# ESP32_Bedsensor_Dual_with_BME_30pin.net
KiCad netlist of a schematic drawn in EasyEDA
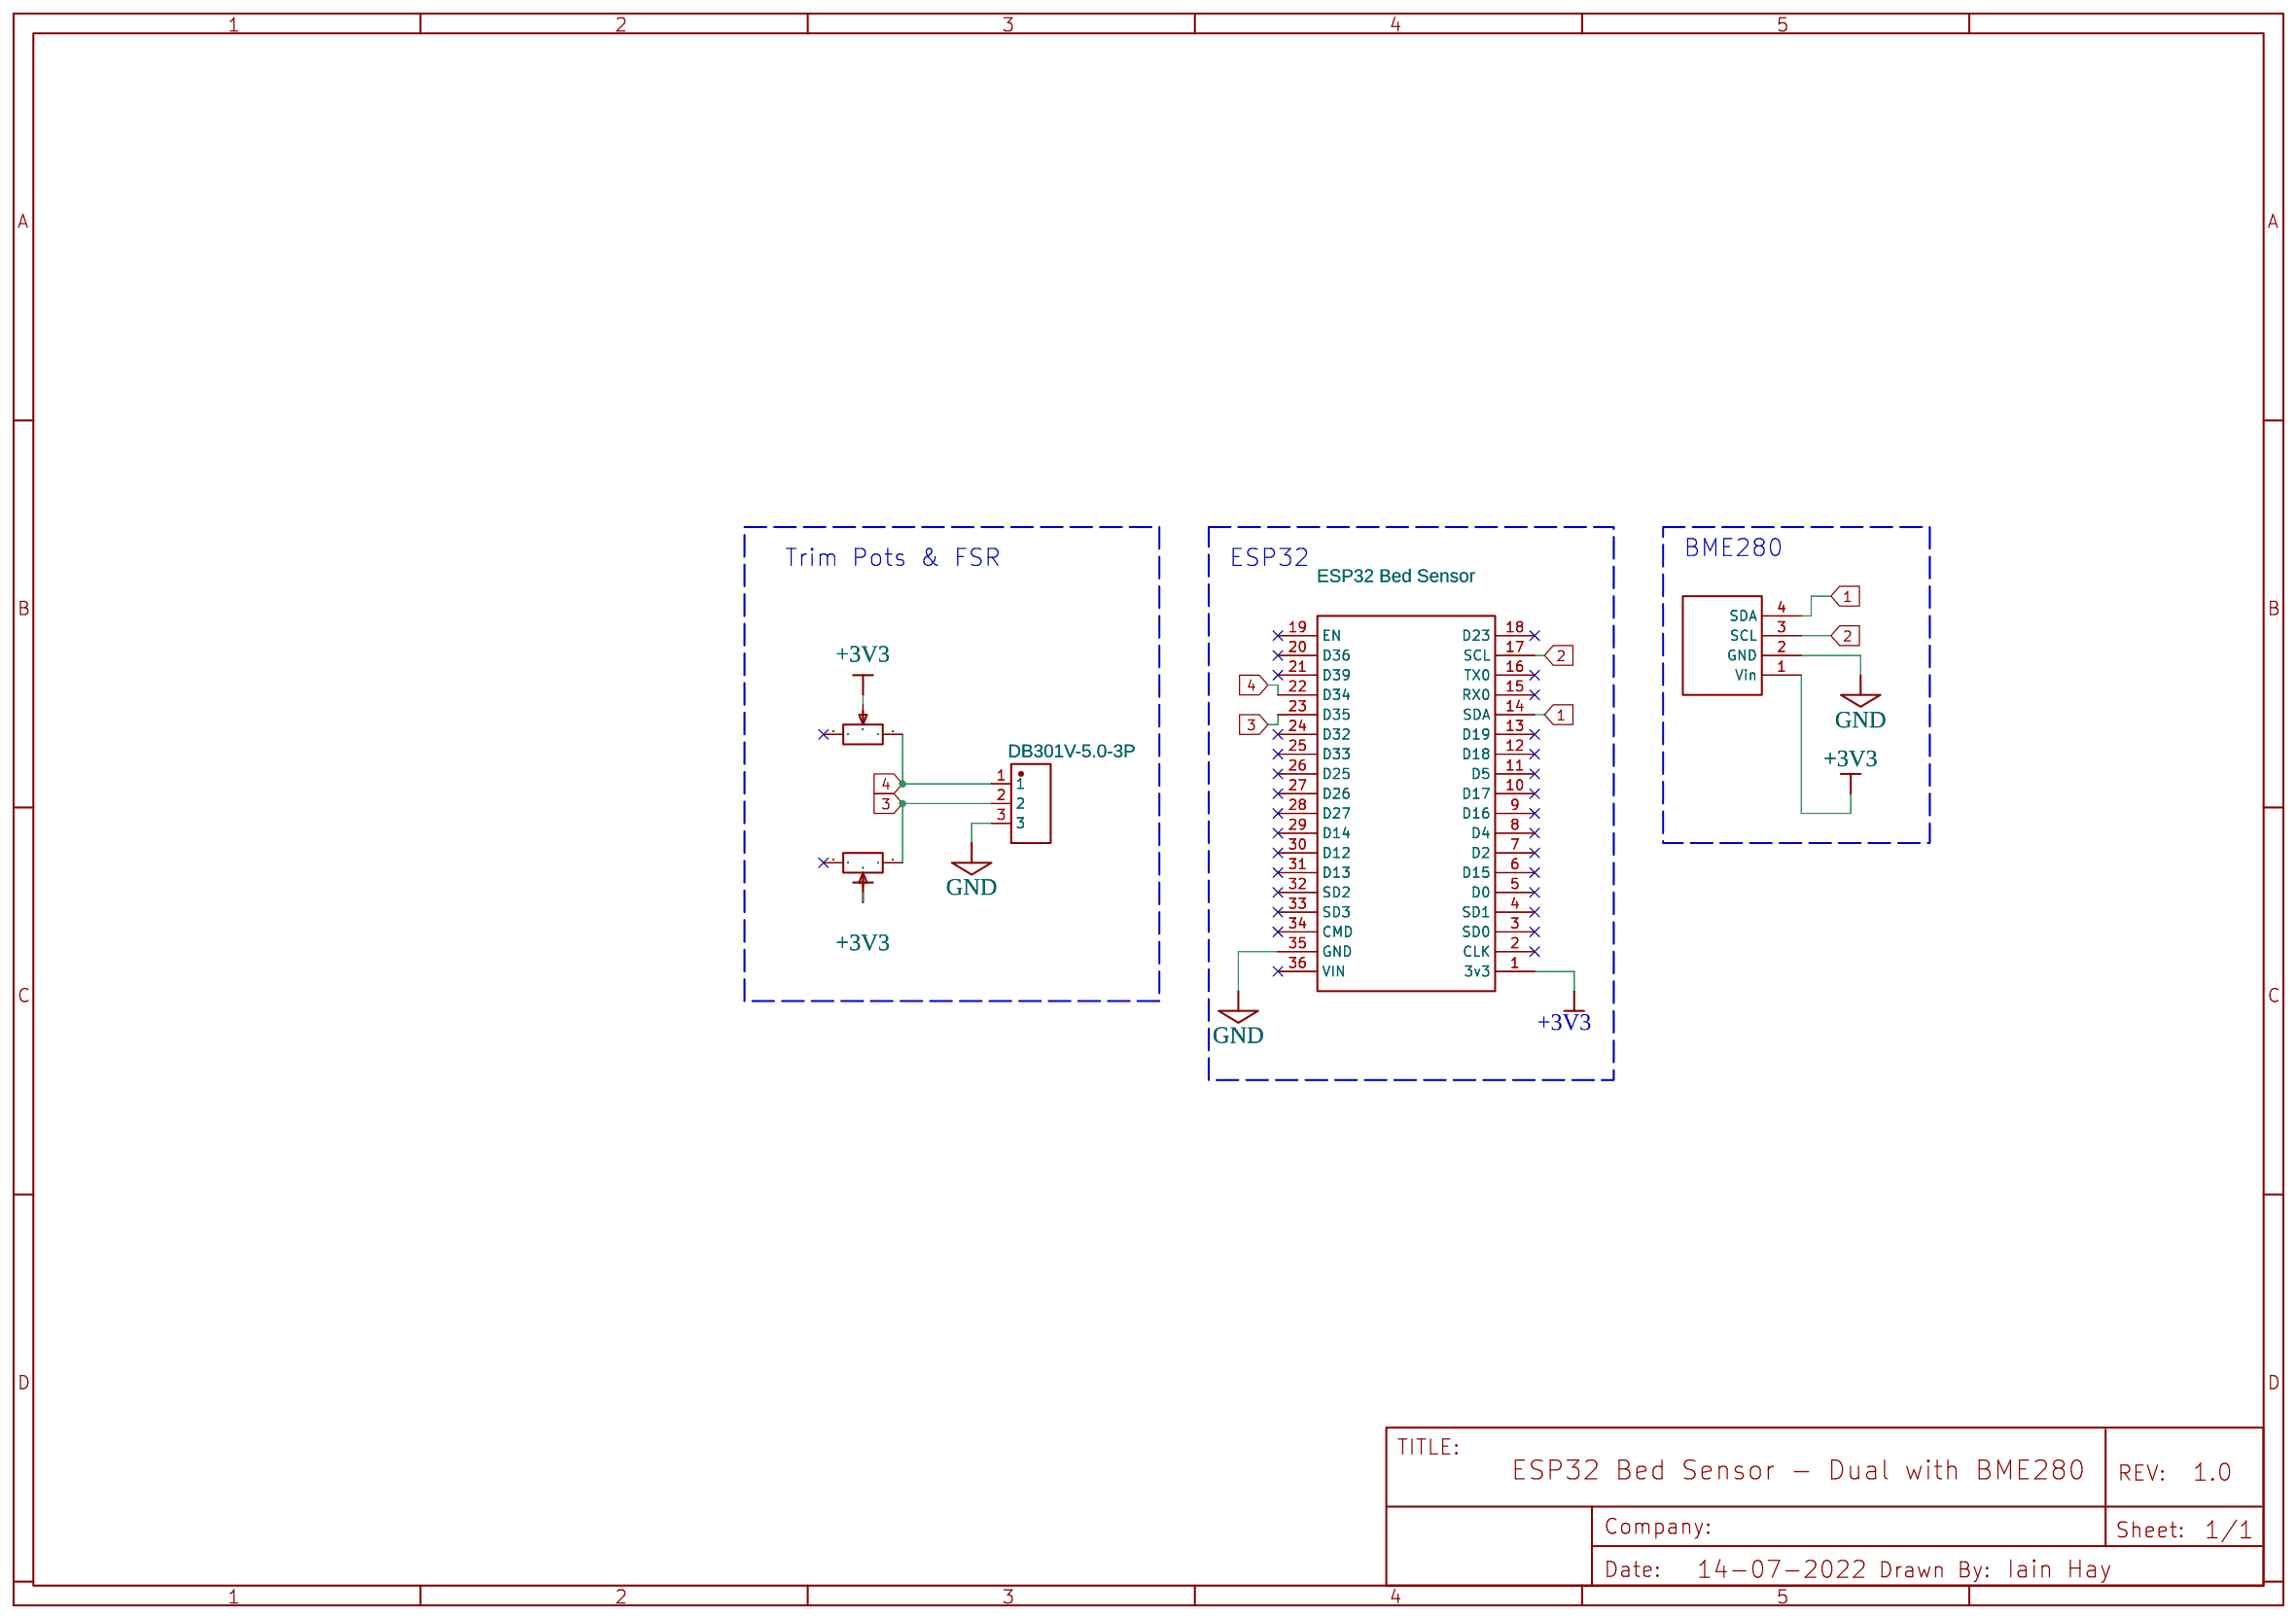
[diagram p0: Schematic]
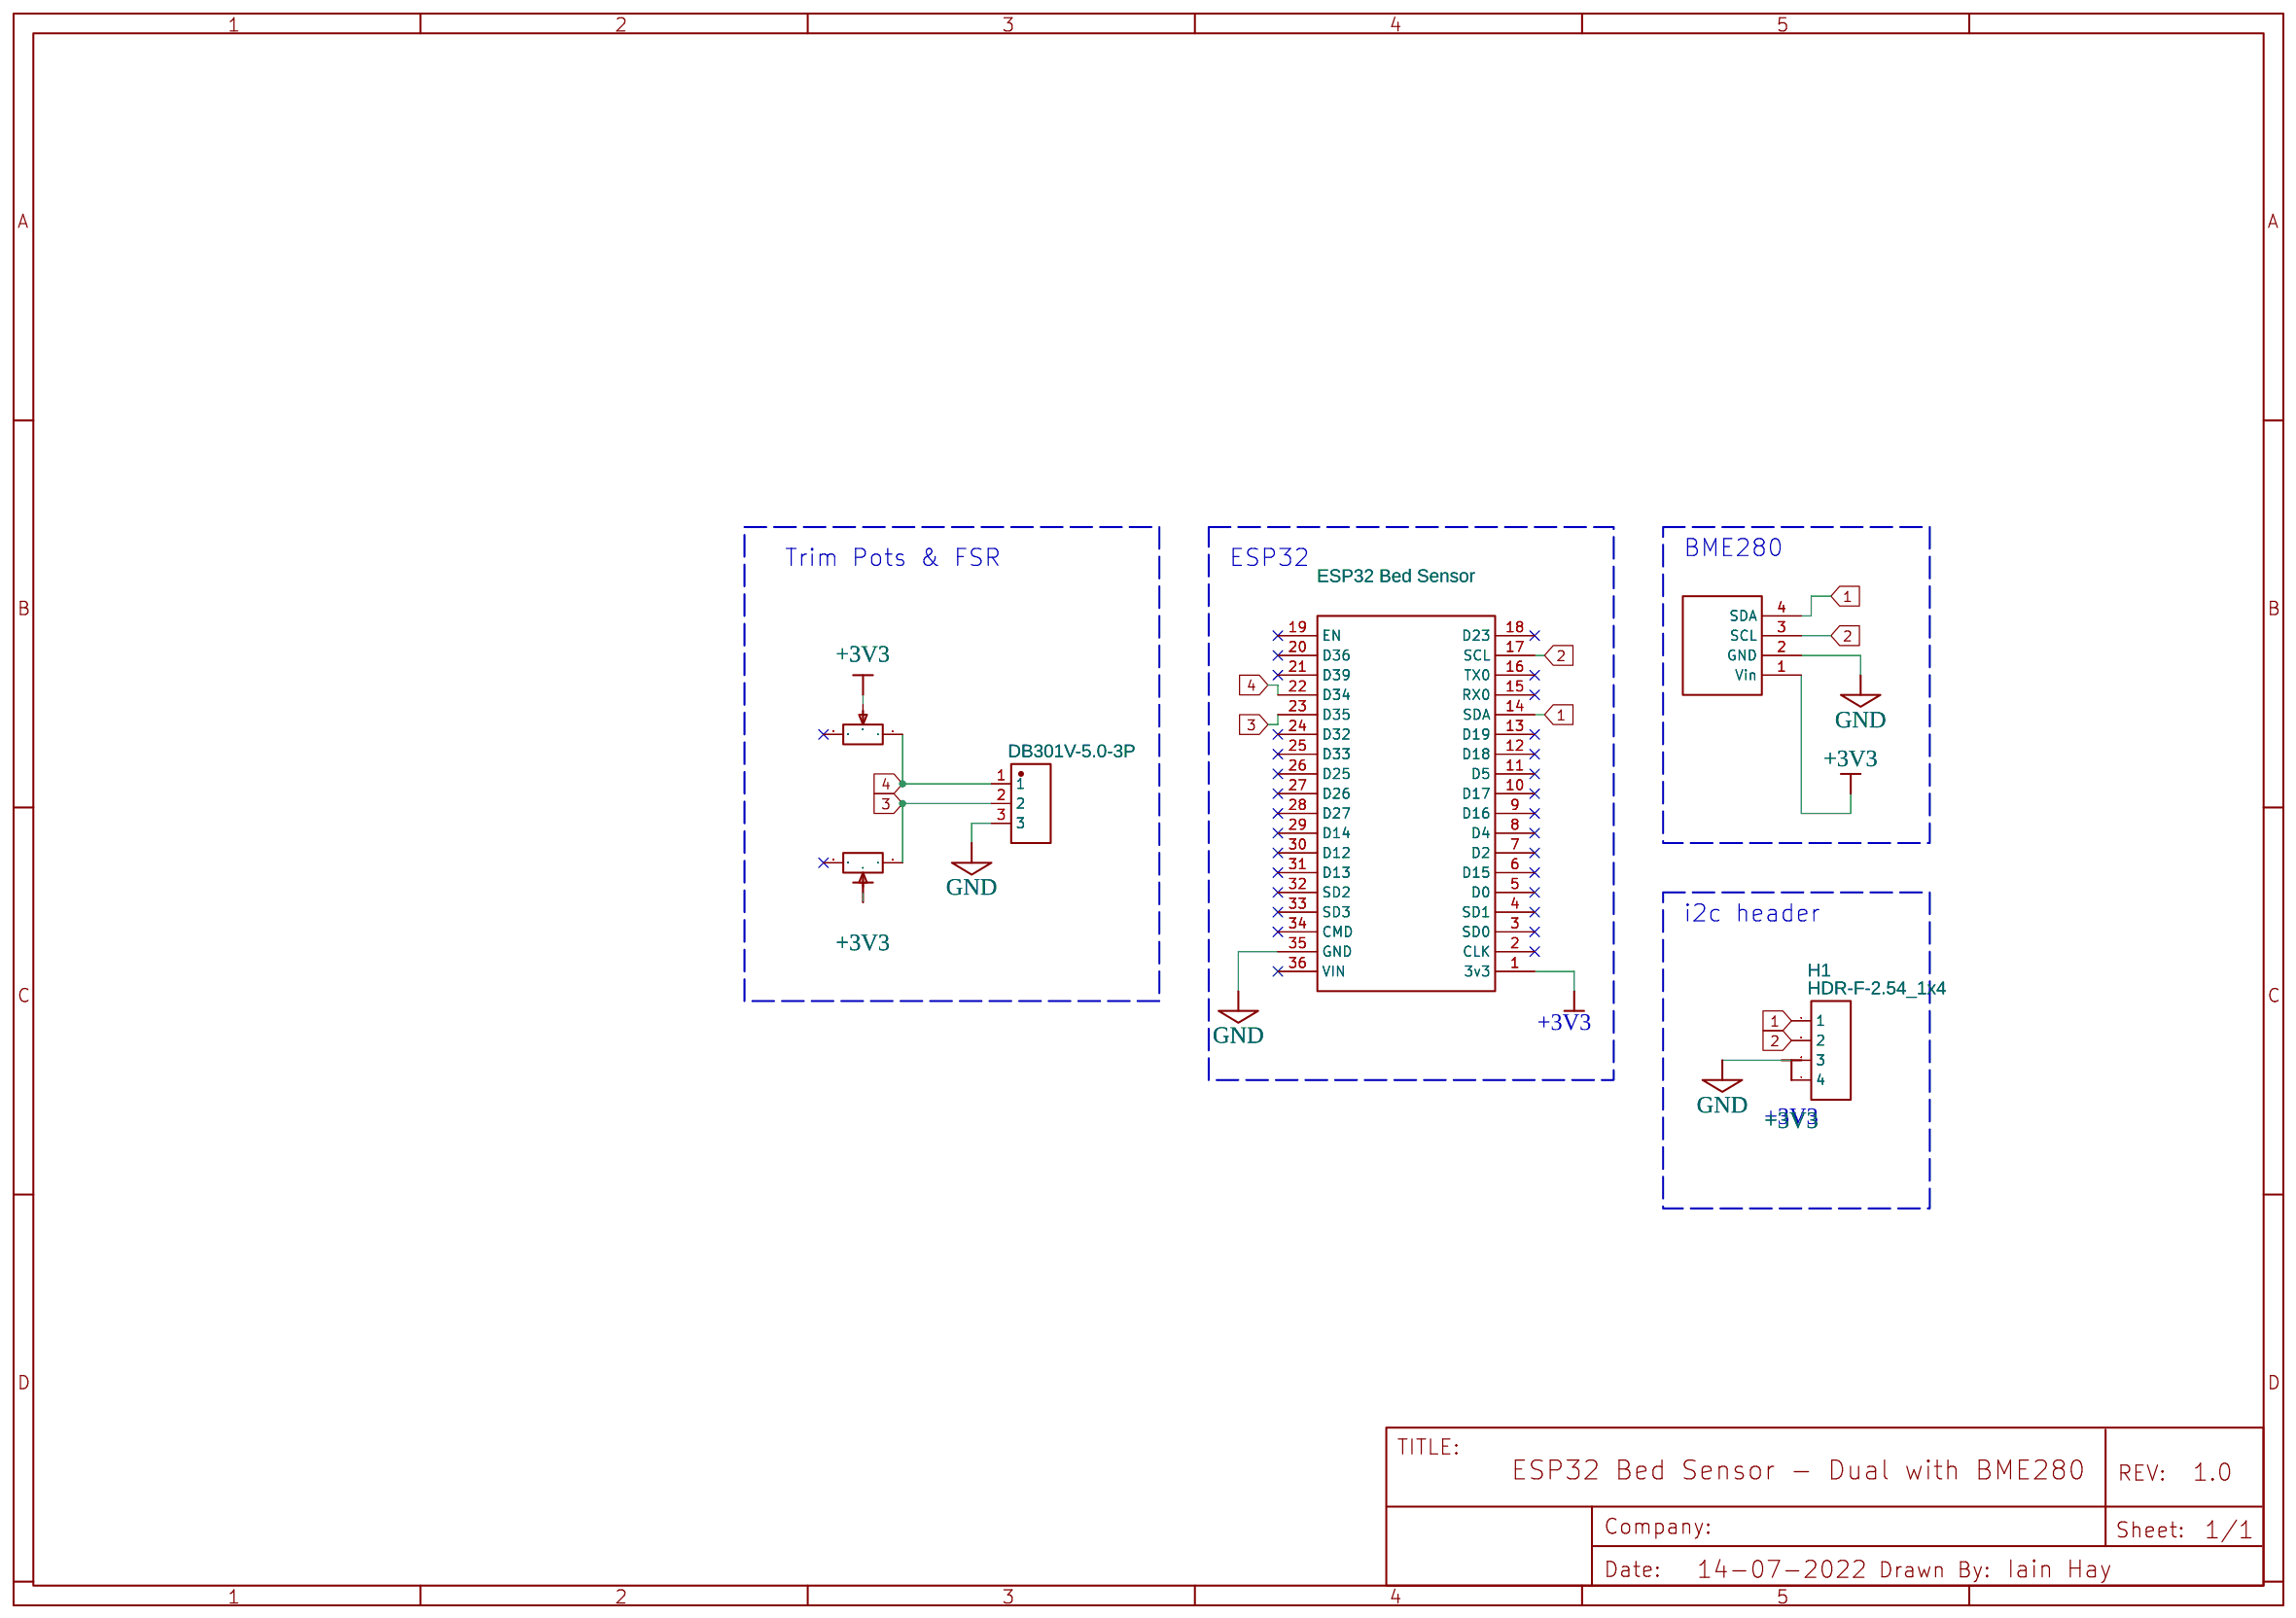
[diagram p1: V2 Schematic]

(export (version "E")
  (design (tool "Eeschema 10.0.6"))
  (components
    (comp (ref "Z1") (value "BME280") (libsource (lib "") (part "BME280")))
    (comp (ref "Z2") (value "ESP32 Bed Sensor") (libsource (lib "") (part "ESP32_DOIT_DEVKIT_V1_36_SHIELD")))
    (comp (ref "Z3")
      (value "DB301V-5.0-3P")
      (fields (field (name "BOM_Supplier Part") "C395881"))
      (libsource (lib "") (part "DB301V-5.0-3P"))
    )
    (comp (ref "Z4")
      (value "RHOS 3296W-1-103LF")
      (fields (field (name "BOM_Supplier Part") "undefined"))
      (libsource (lib "") (part "RHOS 3296W-1-103LF"))
    )
    (comp (ref "Z5")
      (value "RHOS 3296W-1-103LF")
      (fields (field (name "BOM_Supplier Part") "undefined"))
      (libsource (lib "") (part "RHOS 3296W-1-103LF_1"))
    )
    (comp (ref "H1")
      (value "HDR-F-2.54_1x4")
      (fields (field (name "BOM_Supplier Part") "C225501"))
      (libsource (lib "") (part "HDR-F-2.54_1x4"))
    )
    (comp (ref "Z6") (value "BME280") (libsource (lib "") (part "BME280")))
    (comp (ref "Z7") (value "ESP32 Bed Sensor") (libsource (lib "") (part "ESP32_DOIT_DEVKIT_V1_36_SHIELD")))
    (comp (ref "Z8")
      (value "DB301V-5.0-3P")
      (fields (field (name "BOM_Supplier Part") "C395881"))
      (libsource (lib "") (part "DB301V-5.0-3P"))
    )
    (comp (ref "Z9")
      (value "RHOS 3296W-1-103LF")
      (fields (field (name "BOM_Supplier Part") "undefined"))
      (libsource (lib "") (part "RHOS 3296W-1-103LF"))
    )
    (comp (ref "Z10")
      (value "RHOS 3296W-1-103LF")
      (fields (field (name "BOM_Supplier Part") "undefined"))
      (libsource (lib "") (part "RHOS 3296W-1-103LF_1"))
    )
  )
  (nets
    (net (code "1") (name "+3V3") (class "Default")
      (node (ref "H1") (pin "4") (pinfunction "4_4") (pintype "unspecified"))
      (node (ref "Z1") (pin "1") (pinfunction "Vin_1") (pintype "unspecified"))
      (node (ref "Z10") (pin "2") (pinfunction "2_2") (pintype "input"))
      (node (ref "Z2") (pin "1") (pinfunction "3v3_1") (pintype "unspecified"))
      (node (ref "Z4") (pin "2") (pinfunction "2_2") (pintype "input"))
      (node (ref "Z5") (pin "2") (pinfunction "2_2") (pintype "input"))
      (node (ref "Z6") (pin "1") (pinfunction "Vin_1") (pintype "unspecified"))
      (node (ref "Z7") (pin "1") (pinfunction "3v3_1") (pintype "unspecified"))
      (node (ref "Z9") (pin "2") (pinfunction "2_2") (pintype "input"))
    )
    (net (code "2") (name "1") (class "Default")
      (node (ref "H1") (pin "1") (pinfunction "1_1") (pintype "unspecified"))
      (node (ref "Z1") (pin "4") (pinfunction "SDA_4") (pintype "unspecified"))
      (node (ref "Z2") (pin "14") (pinfunction "SDA_14") (pintype "unspecified"))
      (node (ref "Z6") (pin "4") (pinfunction "SDA_4") (pintype "unspecified"))
      (node (ref "Z7") (pin "14") (pinfunction "SDA_14") (pintype "unspecified"))
    )
    (net (code "3") (name "2") (class "Default")
      (node (ref "H1") (pin "2") (pinfunction "2_2") (pintype "unspecified"))
      (node (ref "Z1") (pin "3") (pinfunction "SCL_3") (pintype "unspecified"))
      (node (ref "Z2") (pin "17") (pinfunction "SCL_17") (pintype "unspecified"))
      (node (ref "Z6") (pin "3") (pinfunction "SCL_3") (pintype "unspecified"))
      (node (ref "Z7") (pin "17") (pinfunction "SCL_17") (pintype "unspecified"))
    )
    (net (code "4") (name "3") (class "Default")
      (node (ref "Z10") (pin "1") (pinfunction "1_1") (pintype "input"))
      (node (ref "Z2") (pin "23") (pinfunction "D35_23") (pintype "unspecified"))
      (node (ref "Z3") (pin "2") (pinfunction "2_2") (pintype "unspecified"))
      (node (ref "Z5") (pin "1") (pinfunction "1_1") (pintype "input"))
      (node (ref "Z7") (pin "23") (pinfunction "D35_23") (pintype "unspecified"))
      (node (ref "Z8") (pin "2") (pinfunction "2_2") (pintype "unspecified"))
    )
    (net (code "5") (name "4") (class "Default")
      (node (ref "Z2") (pin "22") (pinfunction "D34_22") (pintype "unspecified"))
      (node (ref "Z3") (pin "1") (pinfunction "1_1") (pintype "unspecified"))
      (node (ref "Z4") (pin "1") (pinfunction "1_1") (pintype "input"))
      (node (ref "Z7") (pin "22") (pinfunction "D34_22") (pintype "unspecified"))
      (node (ref "Z8") (pin "1") (pinfunction "1_1") (pintype "unspecified"))
      (node (ref "Z9") (pin "1") (pinfunction "1_1") (pintype "input"))
    )
    (net (code "6") (name "GND") (class "Default")
      (node (ref "H1") (pin "3") (pinfunction "3_3") (pintype "unspecified"))
      (node (ref "Z1") (pin "2") (pinfunction "GND_2") (pintype "unspecified"))
      (node (ref "Z2") (pin "35") (pinfunction "GND_35") (pintype "unspecified"))
      (node (ref "Z3") (pin "3") (pinfunction "3_3") (pintype "unspecified"))
      (node (ref "Z6") (pin "2") (pinfunction "GND_2") (pintype "unspecified"))
      (node (ref "Z7") (pin "35") (pinfunction "GND_35") (pintype "unspecified"))
      (node (ref "Z8") (pin "3") (pinfunction "3_3") (pintype "unspecified"))
    )
    (net (code "7") (name "unconnected-(Z2-CLK-Pad2)") (class "Default")
      (node (ref "Z2") (pin "2") (pinfunction "CLK_2") (pintype "unspecified+no_connect"))
    )
    (net (code "8") (name "unconnected-(Z2-CMD-Pad34)") (class "Default")
      (node (ref "Z2") (pin "34") (pinfunction "CMD_34") (pintype "unspecified+no_connect"))
    )
    (net (code "9") (name "unconnected-(Z2-D0-Pad5)") (class "Default")
      (node (ref "Z2") (pin "5") (pinfunction "D0_5") (pintype "unspecified+no_connect"))
    )
    (net (code "10") (name "unconnected-(Z2-D2-Pad7)") (class "Default")
      (node (ref "Z2") (pin "7") (pinfunction "D2_7") (pintype "unspecified+no_connect"))
    )
    (net (code "11") (name "unconnected-(Z2-D4-Pad8)") (class "Default")
      (node (ref "Z2") (pin "8") (pinfunction "D4_8") (pintype "unspecified+no_connect"))
    )
    (net (code "12") (name "unconnected-(Z2-D5-Pad11)") (class "Default")
      (node (ref "Z2") (pin "11") (pinfunction "D5_11") (pintype "unspecified+no_connect"))
    )
    (net (code "13") (name "unconnected-(Z2-D12-Pad30)") (class "Default")
      (node (ref "Z2") (pin "30") (pinfunction "D12_30") (pintype "unspecified+no_connect"))
    )
    (net (code "14") (name "unconnected-(Z2-D13-Pad31)") (class "Default")
      (node (ref "Z2") (pin "31") (pinfunction "D13_31") (pintype "unspecified+no_connect"))
    )
    (net (code "15") (name "unconnected-(Z2-D14-Pad29)") (class "Default")
      (node (ref "Z2") (pin "29") (pinfunction "D14_29") (pintype "unspecified+no_connect"))
    )
    (net (code "16") (name "unconnected-(Z2-D15-Pad6)") (class "Default")
      (node (ref "Z2") (pin "6") (pinfunction "D15_6") (pintype "unspecified+no_connect"))
    )
    (net (code "17") (name "unconnected-(Z2-D16-Pad9)") (class "Default")
      (node (ref "Z2") (pin "9") (pinfunction "D16_9") (pintype "unspecified+no_connect"))
    )
    (net (code "18") (name "unconnected-(Z2-D17-Pad10)") (class "Default")
      (node (ref "Z2") (pin "10") (pinfunction "D17_10") (pintype "unspecified+no_connect"))
    )
    (net (code "19") (name "unconnected-(Z2-D18-Pad12)") (class "Default")
      (node (ref "Z2") (pin "12") (pinfunction "D18_12") (pintype "unspecified+no_connect"))
    )
    (net (code "20") (name "unconnected-(Z2-D19-Pad13)") (class "Default")
      (node (ref "Z2") (pin "13") (pinfunction "D19_13") (pintype "unspecified+no_connect"))
    )
    (net (code "21") (name "unconnected-(Z2-D23-Pad18)") (class "Default")
      (node (ref "Z2") (pin "18") (pinfunction "D23_18") (pintype "unspecified+no_connect"))
    )
    (net (code "22") (name "unconnected-(Z2-D25-Pad26)") (class "Default")
      (node (ref "Z2") (pin "26") (pinfunction "D25_26") (pintype "unspecified+no_connect"))
    )
    (net (code "23") (name "unconnected-(Z2-D26-Pad27)") (class "Default")
      (node (ref "Z2") (pin "27") (pinfunction "D26_27") (pintype "unspecified+no_connect"))
    )
    (net (code "24") (name "unconnected-(Z2-D27-Pad28)") (class "Default")
      (node (ref "Z2") (pin "28") (pinfunction "D27_28") (pintype "unspecified+no_connect"))
    )
    (net (code "25") (name "unconnected-(Z2-D32-Pad24)") (class "Default")
      (node (ref "Z2") (pin "24") (pinfunction "D32_24") (pintype "unspecified+no_connect"))
    )
    (net (code "26") (name "unconnected-(Z2-D33-Pad25)") (class "Default")
      (node (ref "Z2") (pin "25") (pinfunction "D33_25") (pintype "unspecified+no_connect"))
    )
    (net (code "27") (name "unconnected-(Z2-D36-Pad20)") (class "Default")
      (node (ref "Z2") (pin "20") (pinfunction "D36_20") (pintype "unspecified+no_connect"))
    )
    (net (code "28") (name "unconnected-(Z2-D39-Pad21)") (class "Default")
      (node (ref "Z2") (pin "21") (pinfunction "D39_21") (pintype "unspecified+no_connect"))
    )
    (net (code "29") (name "unconnected-(Z2-EN-Pad19)") (class "Default")
      (node (ref "Z2") (pin "19") (pinfunction "EN_19") (pintype "unspecified+no_connect"))
    )
    (net (code "30") (name "unconnected-(Z2-RX0-Pad15)") (class "Default")
      (node (ref "Z2") (pin "15") (pinfunction "RX0_15") (pintype "unspecified+no_connect"))
    )
    (net (code "31") (name "unconnected-(Z2-SD0-Pad3)") (class "Default")
      (node (ref "Z2") (pin "3") (pinfunction "SD0_3") (pintype "unspecified+no_connect"))
    )
    (net (code "32") (name "unconnected-(Z2-SD1-Pad4)") (class "Default")
      (node (ref "Z2") (pin "4") (pinfunction "SD1_4") (pintype "unspecified+no_connect"))
    )
    (net (code "33") (name "unconnected-(Z2-SD2-Pad32)") (class "Default")
      (node (ref "Z2") (pin "32") (pinfunction "SD2_32") (pintype "unspecified+no_connect"))
    )
    (net (code "34") (name "unconnected-(Z2-SD3-Pad33)") (class "Default")
      (node (ref "Z2") (pin "33") (pinfunction "SD3_33") (pintype "unspecified+no_connect"))
    )
    (net (code "35") (name "unconnected-(Z2-TX0-Pad16)") (class "Default")
      (node (ref "Z2") (pin "16") (pinfunction "TX0_16") (pintype "unspecified+no_connect"))
    )
    (net (code "36") (name "unconnected-(Z2-VIN-Pad36)") (class "Default")
      (node (ref "Z2") (pin "36") (pinfunction "VIN_36") (pintype "unspecified+no_connect"))
    )
    (net (code "37") (name "unconnected-(Z4-Pad3)") (class "Default")
      (node (ref "Z4") (pin "3") (pinfunction "3_3") (pintype "input+no_connect"))
    )
    (net (code "38") (name "unconnected-(Z5-Pad3)") (class "Default")
      (node (ref "Z5") (pin "3") (pinfunction "3_3") (pintype "input+no_connect"))
    )
    (net (code "39") (name "unconnected-(Z7-CLK-Pad2)") (class "Default")
      (node (ref "Z7") (pin "2") (pinfunction "CLK_2") (pintype "unspecified+no_connect"))
    )
    (net (code "40") (name "unconnected-(Z7-CMD-Pad34)") (class "Default")
      (node (ref "Z7") (pin "34") (pinfunction "CMD_34") (pintype "unspecified+no_connect"))
    )
    (net (code "41") (name "unconnected-(Z7-D0-Pad5)") (class "Default")
      (node (ref "Z7") (pin "5") (pinfunction "D0_5") (pintype "unspecified+no_connect"))
    )
    (net (code "42") (name "unconnected-(Z7-D2-Pad7)") (class "Default")
      (node (ref "Z7") (pin "7") (pinfunction "D2_7") (pintype "unspecified+no_connect"))
    )
    (net (code "43") (name "unconnected-(Z7-D4-Pad8)") (class "Default")
      (node (ref "Z7") (pin "8") (pinfunction "D4_8") (pintype "unspecified+no_connect"))
    )
    (net (code "44") (name "unconnected-(Z7-D5-Pad11)") (class "Default")
      (node (ref "Z7") (pin "11") (pinfunction "D5_11") (pintype "unspecified+no_connect"))
    )
    (net (code "45") (name "unconnected-(Z7-D12-Pad30)") (class "Default")
      (node (ref "Z7") (pin "30") (pinfunction "D12_30") (pintype "unspecified+no_connect"))
    )
    (net (code "46") (name "unconnected-(Z7-D13-Pad31)") (class "Default")
      (node (ref "Z7") (pin "31") (pinfunction "D13_31") (pintype "unspecified+no_connect"))
    )
    (net (code "47") (name "unconnected-(Z7-D14-Pad29)") (class "Default")
      (node (ref "Z7") (pin "29") (pinfunction "D14_29") (pintype "unspecified+no_connect"))
    )
    (net (code "48") (name "unconnected-(Z7-D15-Pad6)") (class "Default")
      (node (ref "Z7") (pin "6") (pinfunction "D15_6") (pintype "unspecified+no_connect"))
    )
    (net (code "49") (name "unconnected-(Z7-D16-Pad9)") (class "Default")
      (node (ref "Z7") (pin "9") (pinfunction "D16_9") (pintype "unspecified+no_connect"))
    )
    (net (code "50") (name "unconnected-(Z7-D17-Pad10)") (class "Default")
      (node (ref "Z7") (pin "10") (pinfunction "D17_10") (pintype "unspecified+no_connect"))
    )
    (net (code "51") (name "unconnected-(Z7-D18-Pad12)") (class "Default")
      (node (ref "Z7") (pin "12") (pinfunction "D18_12") (pintype "unspecified+no_connect"))
    )
    (net (code "52") (name "unconnected-(Z7-D19-Pad13)") (class "Default")
      (node (ref "Z7") (pin "13") (pinfunction "D19_13") (pintype "unspecified+no_connect"))
    )
    (net (code "53") (name "unconnected-(Z7-D23-Pad18)") (class "Default")
      (node (ref "Z7") (pin "18") (pinfunction "D23_18") (pintype "unspecified+no_connect"))
    )
    (net (code "54") (name "unconnected-(Z7-D25-Pad26)") (class "Default")
      (node (ref "Z7") (pin "26") (pinfunction "D25_26") (pintype "unspecified+no_connect"))
    )
    (net (code "55") (name "unconnected-(Z7-D26-Pad27)") (class "Default")
      (node (ref "Z7") (pin "27") (pinfunction "D26_27") (pintype "unspecified+no_connect"))
    )
    (net (code "56") (name "unconnected-(Z7-D27-Pad28)") (class "Default")
      (node (ref "Z7") (pin "28") (pinfunction "D27_28") (pintype "unspecified+no_connect"))
    )
    (net (code "57") (name "unconnected-(Z7-D32-Pad24)") (class "Default")
      (node (ref "Z7") (pin "24") (pinfunction "D32_24") (pintype "unspecified+no_connect"))
    )
    (net (code "58") (name "unconnected-(Z7-D33-Pad25)") (class "Default")
      (node (ref "Z7") (pin "25") (pinfunction "D33_25") (pintype "unspecified+no_connect"))
    )
    (net (code "59") (name "unconnected-(Z7-D36-Pad20)") (class "Default")
      (node (ref "Z7") (pin "20") (pinfunction "D36_20") (pintype "unspecified+no_connect"))
    )
    (net (code "60") (name "unconnected-(Z7-D39-Pad21)") (class "Default")
      (node (ref "Z7") (pin "21") (pinfunction "D39_21") (pintype "unspecified+no_connect"))
    )
    (net (code "61") (name "unconnected-(Z7-EN-Pad19)") (class "Default")
      (node (ref "Z7") (pin "19") (pinfunction "EN_19") (pintype "unspecified+no_connect"))
    )
    (net (code "62") (name "unconnected-(Z7-RX0-Pad15)") (class "Default")
      (node (ref "Z7") (pin "15") (pinfunction "RX0_15") (pintype "unspecified+no_connect"))
    )
    (net (code "63") (name "unconnected-(Z7-SD0-Pad3)") (class "Default")
      (node (ref "Z7") (pin "3") (pinfunction "SD0_3") (pintype "unspecified+no_connect"))
    )
    (net (code "64") (name "unconnected-(Z7-SD1-Pad4)") (class "Default")
      (node (ref "Z7") (pin "4") (pinfunction "SD1_4") (pintype "unspecified+no_connect"))
    )
    (net (code "65") (name "unconnected-(Z7-SD2-Pad32)") (class "Default")
      (node (ref "Z7") (pin "32") (pinfunction "SD2_32") (pintype "unspecified+no_connect"))
    )
    (net (code "66") (name "unconnected-(Z7-SD3-Pad33)") (class "Default")
      (node (ref "Z7") (pin "33") (pinfunction "SD3_33") (pintype "unspecified+no_connect"))
    )
    (net (code "67") (name "unconnected-(Z7-TX0-Pad16)") (class "Default")
      (node (ref "Z7") (pin "16") (pinfunction "TX0_16") (pintype "unspecified+no_connect"))
    )
    (net (code "68") (name "unconnected-(Z7-VIN-Pad36)") (class "Default")
      (node (ref "Z7") (pin "36") (pinfunction "VIN_36") (pintype "unspecified+no_connect"))
    )
    (net (code "69") (name "unconnected-(Z9-Pad3)") (class "Default")
      (node (ref "Z9") (pin "3") (pinfunction "3_3") (pintype "input+no_connect"))
    )
    (net (code "70") (name "unconnected-(Z10-Pad3)") (class "Default")
      (node (ref "Z10") (pin "3") (pinfunction "3_3") (pintype "input+no_connect"))
    )
  )
)
